# IMU_sheild.net
KiCad netlist of a schematic drawn in Altium Designer
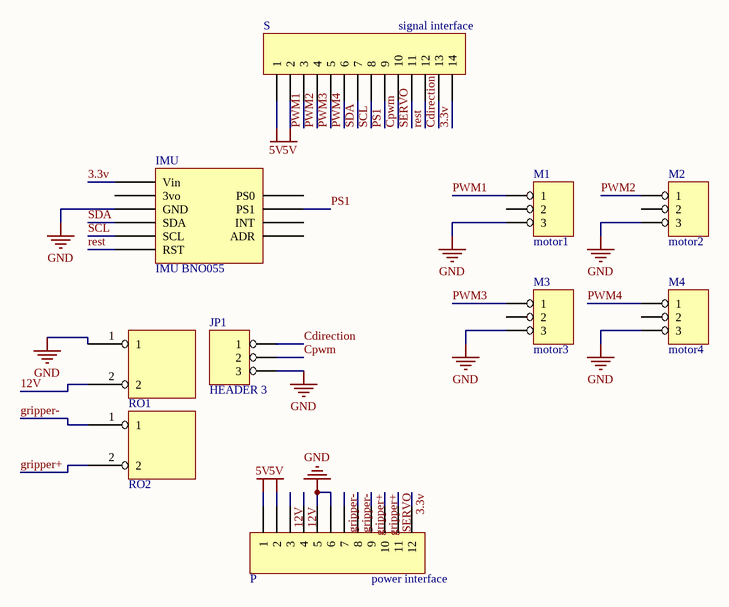
[diagram p0: IMU sheild.SchDoc]

(export (version "E")
  (design (tool "Eeschema 10.0.6"))
  (components
    (comp (ref "IMU")
      (value "IMU BNO055")
      (footprint "bno055")
      (libsource (lib "crocomarine") (part "IMU BNO055"))
    )
    (comp (ref "JP1")
      (value "HEADER 3")
      (footprint "SIP3")
      (libsource (lib "Final Library") (part "HEADER 3"))
    )
    (comp (ref "M1") (value "motor1") (footprint "SIP3") (libsource (lib "") (part "HEADER 3_1")))
    (comp (ref "M2") (value "motor2") (footprint "SIP3") (libsource (lib "") (part "HEADER 3_1")))
    (comp (ref "M3") (value "motor3") (footprint "SIP3") (libsource (lib "") (part "HEADER 3_1")))
    (comp (ref "M4") (value "motor4") (footprint "SIP3") (libsource (lib "") (part "HEADER 3_1")))
    (comp (ref "P")
      (value "power interface")
      (footprint "HDR1X12")
      (description "Header, 12-Pin")
      (fields (field (name "PUBLISHER") "Altium Limited"))
      (libsource (lib "Miscellaneous Connectors") (part "Header 12"))
    )
    (comp (ref "RO1")
      (value "Rossetta")
      (footprint "Rossetta 2-pin")
      (libsource (lib "crocomarine") (part "Rossetta"))
    )
    (comp (ref "RO2")
      (value "Rossetta")
      (footprint "Rossetta 2-pin")
      (libsource (lib "crocomarine") (part "Rossetta"))
    )
    (comp (ref "S")
      (value "signal interface")
      (footprint "HDR1X14")
      (description "Header, 14-Pin")
      (fields (field (name "PUBLISHER") "Altium Limited"))
      (libsource (lib "Miscellaneous Connectors") (part "Header 14"))
    )
  )
  (nets
    (net (code "1") (name "/3.3v") (class "Default")
      (node (ref "IMU") (pin "Vin") (pinfunction "Vin_Vin") (pintype "passive"))
      (node (ref "P") (pin "12") (pinfunction "12_12") (pintype "passive"))
      (node (ref "S") (pin "14") (pinfunction "14_14") (pintype "passive"))
    )
    (net (code "2") (name "/12V") (class "Default")
      (node (ref "P") (pin "3") (pinfunction "3_3") (pintype "passive"))
      (node (ref "P") (pin "4") (pinfunction "4_4") (pintype "passive"))
      (node (ref "RO1") (pin "2") (pinfunction "2_2") (pintype "passive"))
    )
    (net (code "3") (name "/Cdirection") (class "Default")
      (node (ref "JP1") (pin "1") (pinfunction "1_1") (pintype "passive"))
      (node (ref "S") (pin "13") (pinfunction "13_13") (pintype "passive"))
    )
    (net (code "4") (name "/Cpwm") (class "Default")
      (node (ref "JP1") (pin "2") (pinfunction "2_2") (pintype "passive"))
      (node (ref "S") (pin "10") (pinfunction "10_10") (pintype "passive"))
    )
    (net (code "5") (name "/PS1") (class "Default")
      (node (ref "IMU") (pin "ps1") (pinfunction "PS1_ps1") (pintype "passive"))
      (node (ref "S") (pin "9") (pinfunction "9_9") (pintype "passive"))
    )
    (net (code "6") (name "/PWM1") (class "Default")
      (node (ref "M1") (pin "1") (pinfunction "1_1") (pintype "passive"))
      (node (ref "S") (pin "3") (pinfunction "3_3") (pintype "passive"))
    )
    (net (code "7") (name "/PWM2") (class "Default")
      (node (ref "M2") (pin "1") (pinfunction "1_1") (pintype "passive"))
      (node (ref "S") (pin "4") (pinfunction "4_4") (pintype "passive"))
    )
    (net (code "8") (name "/PWM3") (class "Default")
      (node (ref "M3") (pin "1") (pinfunction "1_1") (pintype "passive"))
      (node (ref "S") (pin "5") (pinfunction "5_5") (pintype "passive"))
    )
    (net (code "9") (name "/PWM4") (class "Default")
      (node (ref "M4") (pin "1") (pinfunction "1_1") (pintype "passive"))
      (node (ref "S") (pin "6") (pinfunction "6_6") (pintype "passive"))
    )
    (net (code "10") (name "/SCL") (class "Default")
      (node (ref "IMU") (pin "SCL") (pinfunction "SCL_SCL") (pintype "passive"))
      (node (ref "S") (pin "8") (pinfunction "8_8") (pintype "passive"))
    )
    (net (code "11") (name "/SDA") (class "Default")
      (node (ref "IMU") (pin "SDA") (pinfunction "SDA_SDA") (pintype "passive"))
      (node (ref "S") (pin "7") (pinfunction "7_7") (pintype "passive"))
    )
    (net (code "12") (name "/SERVO") (class "Default")
      (node (ref "P") (pin "11") (pinfunction "11_11") (pintype "passive"))
      (node (ref "S") (pin "11") (pinfunction "11_11") (pintype "passive"))
    )
    (net (code "13") (name "/gripper+") (class "Default")
      (node (ref "P") (pin "10") (pinfunction "10_10") (pintype "passive"))
      (node (ref "P") (pin "9") (pinfunction "9_9") (pintype "passive"))
      (node (ref "RO2") (pin "2") (pinfunction "2_2") (pintype "passive"))
    )
    (net (code "14") (name "/gripper-") (class "Default")
      (node (ref "P") (pin "7") (pinfunction "7_7") (pintype "passive"))
      (node (ref "P") (pin "8") (pinfunction "8_8") (pintype "passive"))
      (node (ref "RO2") (pin "1") (pinfunction "1_1") (pintype "passive"))
    )
    (net (code "15") (name "/rest") (class "Default")
      (node (ref "IMU") (pin "RST") (pinfunction "RST_RST") (pintype "passive"))
      (node (ref "S") (pin "12") (pinfunction "12_12") (pintype "passive"))
    )
    (net (code "16") (name "5V") (class "Default")
      (node (ref "P") (pin "1") (pinfunction "1_1") (pintype "passive"))
      (node (ref "P") (pin "2") (pinfunction "2_2") (pintype "passive"))
      (node (ref "S") (pin "1") (pinfunction "1_1") (pintype "passive"))
      (node (ref "S") (pin "2") (pinfunction "2_2") (pintype "passive"))
    )
    (net (code "17") (name "GND") (class "Default")
      (node (ref "IMU") (pin "GND") (pinfunction "GND_GND") (pintype "passive"))
      (node (ref "JP1") (pin "3") (pinfunction "3_3") (pintype "passive"))
      (node (ref "M1") (pin "3") (pinfunction "3_3") (pintype "passive"))
      (node (ref "M2") (pin "3") (pinfunction "3_3") (pintype "passive"))
      (node (ref "M3") (pin "3") (pinfunction "3_3") (pintype "passive"))
      (node (ref "M4") (pin "3") (pinfunction "3_3") (pintype "passive"))
      (node (ref "P") (pin "5") (pinfunction "5_5") (pintype "passive"))
      (node (ref "P") (pin "6") (pinfunction "6_6") (pintype "passive"))
      (node (ref "RO1") (pin "1") (pinfunction "1_1") (pintype "passive"))
    )
    (net (code "18") (name "unconnected-(IMU-Pad3vo)") (class "Default")
      (node (ref "IMU") (pin "3vo") (pinfunction "3vo_3vo") (pintype "passive"))
    )
    (net (code "19") (name "unconnected-(IMU-PadADR)") (class "Default")
      (node (ref "IMU") (pin "ADR") (pinfunction "ADR_ADR") (pintype "passive"))
    )
    (net (code "20") (name "unconnected-(IMU-PadINT)") (class "Default")
      (node (ref "IMU") (pin "INT") (pinfunction "INT_INT") (pintype "passive"))
    )
    (net (code "21") (name "unconnected-(IMU-PadPS0)") (class "Default")
      (node (ref "IMU") (pin "PS0") (pinfunction "PS0_PS0") (pintype "passive"))
    )
    (net (code "22") (name "unconnected-(M1-Pad2)") (class "Default")
      (node (ref "M1") (pin "2") (pinfunction "2_2") (pintype "passive"))
    )
    (net (code "23") (name "unconnected-(M2-Pad2)") (class "Default")
      (node (ref "M2") (pin "2") (pinfunction "2_2") (pintype "passive"))
    )
    (net (code "24") (name "unconnected-(M3-Pad2)") (class "Default")
      (node (ref "M3") (pin "2") (pinfunction "2_2") (pintype "passive"))
    )
    (net (code "25") (name "unconnected-(M4-Pad2)") (class "Default")
      (node (ref "M4") (pin "2") (pinfunction "2_2") (pintype "passive"))
    )
  )
)
